# panelDoc.net
KiCad netlist of a schematic drawn in EAGLE
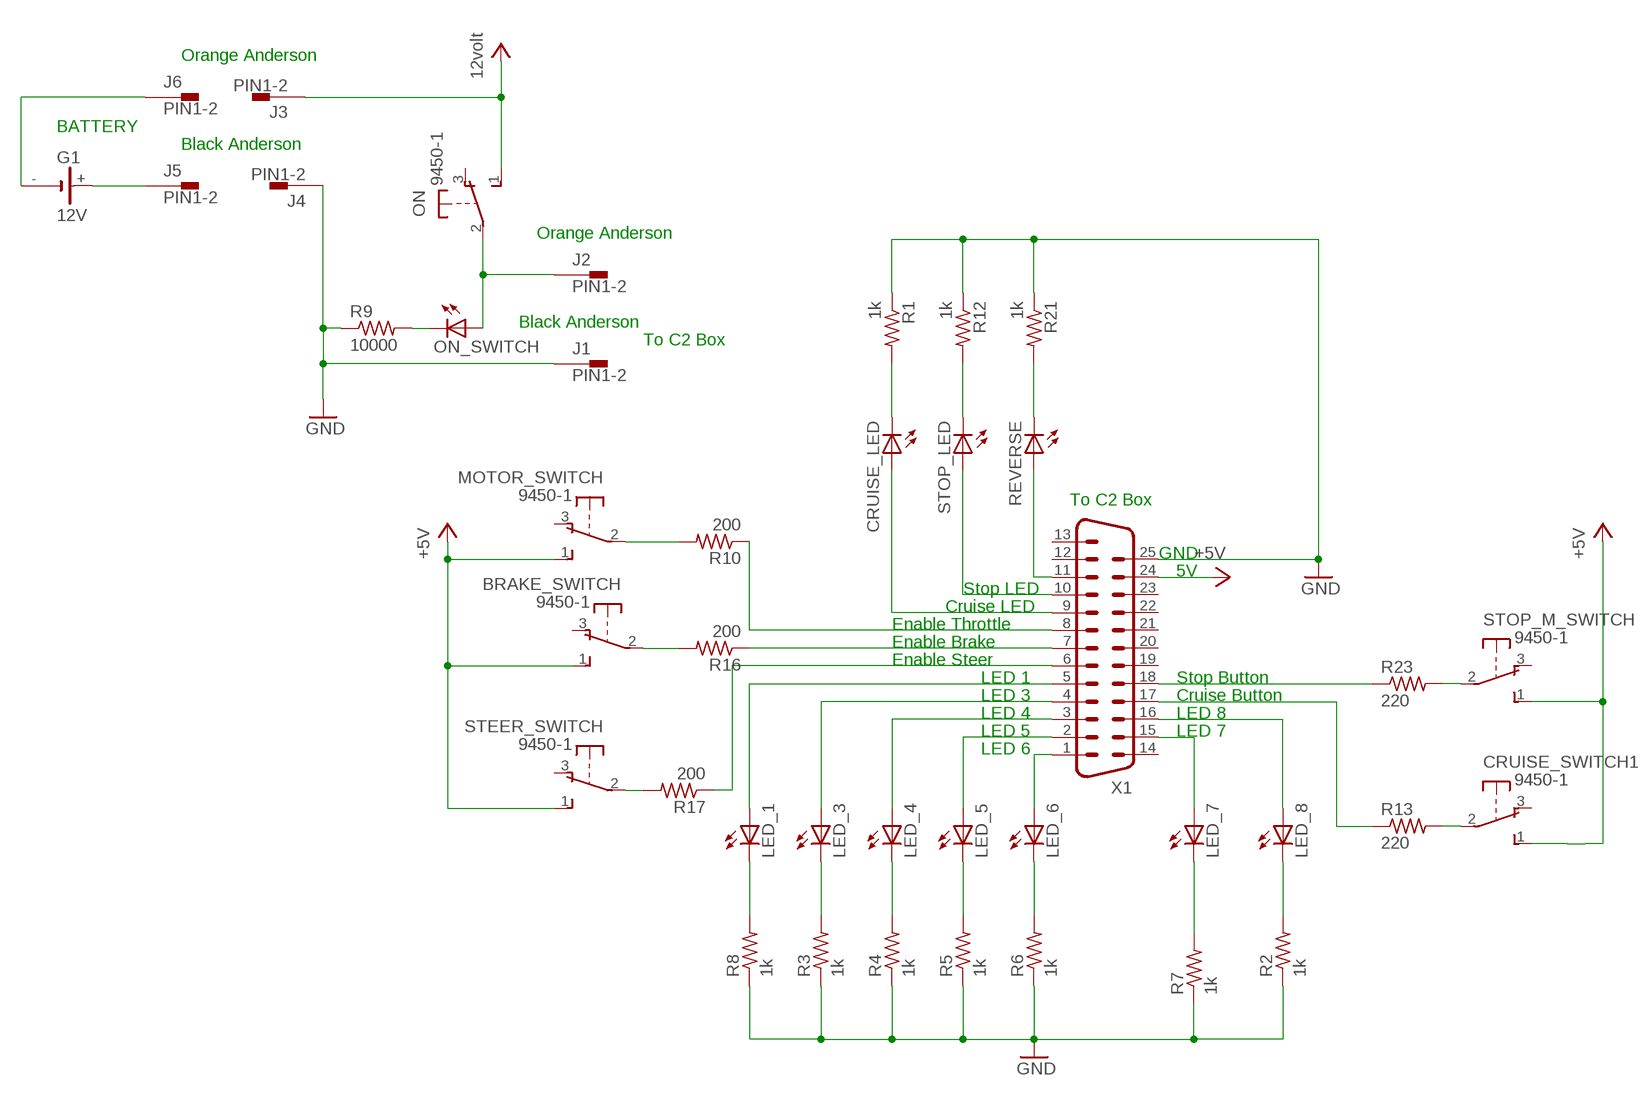
[diagram p0: schematic, sheet 1]

(export (version "E")
  (design (tool "Eeschema 10.0.6"))
  (components
    (comp (ref "BRAKE_SWITCH")
      (value "9450-1")
      (footprint "eagle-import:9450-1")
      (libsource (lib "eagle-import") (part "9450-1"))
    )
    (comp (ref "CRUISE_LED")
      (value "LEDB155")
      (footprint "eagle-import:Q62902-B155")
      (libsource (lib "eagle-import") (part "LEDB155"))
    )
    (comp (ref "CRUISE_SWITCH1")
      (value "9450-1")
      (footprint "eagle-import:9450-1")
      (libsource (lib "eagle-import") (part "9450-1"))
    )
    (comp (ref "G1")
      (value "12V")
      (footprint "eagle-import:SL-150-1_2AA_PT")
      (libsource (lib "eagle-import") (part "SL-150-1/2AA/PT"))
    )
    (comp (ref "J1")
      (value "PIN1-2")
      (footprint "eagle-import:62221")
      (fields (field (name "MF") "TYCO ELECTRONICS") (field (name "MPN") "62221-1"))
      (libsource (lib "eagle-import") (part "PIN1-2"))
    )
    (comp (ref "J2")
      (value "PIN1-2")
      (footprint "eagle-import:62221")
      (fields (field (name "MF") "TYCO ELECTRONICS") (field (name "MPN") "62221-1"))
      (libsource (lib "eagle-import") (part "PIN1-2"))
    )
    (comp (ref "J3")
      (value "PIN1-2")
      (footprint "eagle-import:62221")
      (fields (field (name "MF") "TYCO ELECTRONICS") (field (name "MPN") "62221-1"))
      (libsource (lib "eagle-import") (part "PIN1-2"))
    )
    (comp (ref "J4")
      (value "PIN1-2")
      (footprint "eagle-import:62221")
      (fields (field (name "MF") "TYCO ELECTRONICS") (field (name "MPN") "62221-1"))
      (libsource (lib "eagle-import") (part "PIN1-2"))
    )
    (comp (ref "J5")
      (value "PIN1-2")
      (footprint "eagle-import:62221")
      (fields (field (name "MF") "TYCO ELECTRONICS") (field (name "MPN") "62221-1"))
      (libsource (lib "eagle-import") (part "PIN1-2"))
    )
    (comp (ref "J6")
      (value "PIN1-2")
      (footprint "eagle-import:62221")
      (fields (field (name "MF") "TYCO ELECTRONICS") (field (name "MPN") "62221-1"))
      (libsource (lib "eagle-import") (part "PIN1-2"))
    )
    (comp (ref "LED_1")
      (value "LEDB155")
      (footprint "eagle-import:Q62902-B155")
      (libsource (lib "eagle-import") (part "LEDB155"))
    )
    (comp (ref "LED_3")
      (value "LEDB155")
      (footprint "eagle-import:Q62902-B155")
      (libsource (lib "eagle-import") (part "LEDB155"))
    )
    (comp (ref "LED_4")
      (value "LEDB155")
      (footprint "eagle-import:Q62902-B155")
      (libsource (lib "eagle-import") (part "LEDB155"))
    )
    (comp (ref "LED_5")
      (value "LEDB155")
      (footprint "eagle-import:Q62902-B155")
      (libsource (lib "eagle-import") (part "LEDB155"))
    )
    (comp (ref "LED_6")
      (value "LEDB155")
      (footprint "eagle-import:Q62902-B155")
      (libsource (lib "eagle-import") (part "LEDB155"))
    )
    (comp (ref "LED_7")
      (value "LEDB155")
      (footprint "eagle-import:Q62902-B155")
      (libsource (lib "eagle-import") (part "LEDB155"))
    )
    (comp (ref "LED_8")
      (value "LEDB155")
      (footprint "eagle-import:Q62902-B155")
      (libsource (lib "eagle-import") (part "LEDB155"))
    )
    (comp (ref "MOTOR_SWITCH")
      (value "9450-1")
      (footprint "eagle-import:9450-1")
      (libsource (lib "eagle-import") (part "9450-1"))
    )
    (comp (ref "ON")
      (value "9450-1")
      (footprint "eagle-import:9450-1")
      (libsource (lib "eagle-import") (part "9450-1"))
    )
    (comp (ref "ON_SWITCH")
      (value "LEDB155")
      (footprint "eagle-import:Q62902-B155")
      (libsource (lib "eagle-import") (part "LEDB155"))
    )
    (comp (ref "R1")
      (value "1k")
      (footprint "eagle-import:0617_17")
      (libsource (lib "eagle-import") (part "R-US_0617/17"))
    )
    (comp (ref "R2")
      (value "1k")
      (footprint "eagle-import:0617_17")
      (libsource (lib "eagle-import") (part "R-US_0617/17"))
    )
    (comp (ref "R3")
      (value "1k")
      (footprint "eagle-import:0617_17")
      (libsource (lib "eagle-import") (part "R-US_0617/17"))
    )
    (comp (ref "R4")
      (value "1k")
      (footprint "eagle-import:0617_17")
      (libsource (lib "eagle-import") (part "R-US_0617/17"))
    )
    (comp (ref "R5")
      (value "1k")
      (footprint "eagle-import:0617_17")
      (libsource (lib "eagle-import") (part "R-US_0617/17"))
    )
    (comp (ref "R6")
      (value "1k")
      (footprint "eagle-import:0617_17")
      (libsource (lib "eagle-import") (part "R-US_0617/17"))
    )
    (comp (ref "R7")
      (value "1k")
      (footprint "eagle-import:0617_17")
      (libsource (lib "eagle-import") (part "R-US_0617/17"))
    )
    (comp (ref "R8")
      (value "1k")
      (footprint "eagle-import:0617_17")
      (libsource (lib "eagle-import") (part "R-US_0617/17"))
    )
    (comp (ref "R9")
      (value "10000")
      (footprint "eagle-import:0617_17")
      (libsource (lib "eagle-import") (part "R-US_0617/17"))
    )
    (comp (ref "R10")
      (value "200")
      (footprint "eagle-import:0617_17")
      (libsource (lib "eagle-import") (part "R-US_0617/17"))
    )
    (comp (ref "R12")
      (value "1k")
      (footprint "eagle-import:0617_17")
      (libsource (lib "eagle-import") (part "R-US_0617/17"))
    )
    (comp (ref "R13")
      (value "220")
      (footprint "eagle-import:0617_17")
      (libsource (lib "eagle-import") (part "R-US_0617/17"))
    )
    (comp (ref "R16")
      (value "200")
      (footprint "eagle-import:0617_17")
      (libsource (lib "eagle-import") (part "R-US_0617/17"))
    )
    (comp (ref "R17")
      (value "200")
      (footprint "eagle-import:0617_17")
      (libsource (lib "eagle-import") (part "R-US_0617/17"))
    )
    (comp (ref "R21")
      (value "1k")
      (footprint "eagle-import:0617_17")
      (libsource (lib "eagle-import") (part "R-US_0617/17"))
    )
    (comp (ref "R23")
      (value "220")
      (footprint "eagle-import:0617_17")
      (libsource (lib "eagle-import") (part "R-US_0617/17"))
    )
    (comp (ref "REVERSE")
      (value "LEDB155")
      (footprint "eagle-import:Q62902-B155")
      (libsource (lib "eagle-import") (part "LEDB155"))
    )
    (comp (ref "STEER_SWITCH")
      (value "9450-1")
      (footprint "eagle-import:9450-1")
      (libsource (lib "eagle-import") (part "9450-1"))
    )
    (comp (ref "STOP_LED")
      (value "LEDB155")
      (footprint "eagle-import:Q62902-B155")
      (libsource (lib "eagle-import") (part "LEDB155"))
    )
    (comp (ref "STOP_M_SWITCH")
      (value "9450-1")
      (footprint "eagle-import:9450-1")
      (libsource (lib "eagle-import") (part "9450-1"))
    )
    (comp (ref "X1")
      (value "M25-182")
      (footprint "eagle-import:182-025-MALE")
      (libsource (lib "eagle-import") (part "M25-182"))
    )
  )
  (nets
    (net (code "1") (name "+5V") (class "Default")
      (node (ref "BRAKE_SWITCH") (pin "1") (pinfunction "S_1") (pintype "passive"))
      (node (ref "CRUISE_SWITCH1") (pin "1") (pinfunction "S_1") (pintype "passive"))
      (node (ref "J3") (pin "1") (pinfunction "1_1") (pintype "passive"))
      (node (ref "MOTOR_SWITCH") (pin "1") (pinfunction "S_1") (pintype "passive"))
      (node (ref "ON") (pin "1") (pinfunction "S_1") (pintype "passive"))
      (node (ref "STEER_SWITCH") (pin "1") (pinfunction "S_1") (pintype "passive"))
      (node (ref "STOP_M_SWITCH") (pin "1") (pinfunction "S_1") (pintype "passive"))
      (node (ref "X1") (pin "24") (pinfunction "24_24") (pintype "passive"))
    )
    (net (code "2") (name "GND") (class "Default")
      (node (ref "J1") (pin "1") (pinfunction "1_1") (pintype "passive"))
      (node (ref "J4") (pin "1") (pinfunction "1_1") (pintype "passive"))
      (node (ref "R1") (pin "1") (pinfunction "1_1") (pintype "passive"))
      (node (ref "R12") (pin "1") (pinfunction "1_1") (pintype "passive"))
      (node (ref "R2") (pin "1") (pinfunction "1_1") (pintype "passive"))
      (node (ref "R21") (pin "1") (pinfunction "1_1") (pintype "passive"))
      (node (ref "R3") (pin "1") (pinfunction "1_1") (pintype "passive"))
      (node (ref "R4") (pin "1") (pinfunction "1_1") (pintype "passive"))
      (node (ref "R5") (pin "1") (pinfunction "1_1") (pintype "passive"))
      (node (ref "R6") (pin "1") (pinfunction "1_1") (pintype "passive"))
      (node (ref "R7") (pin "1") (pinfunction "1_1") (pintype "passive"))
      (node (ref "R8") (pin "1") (pinfunction "1_1") (pintype "passive"))
      (node (ref "R9") (pin "1") (pinfunction "1_1") (pintype "passive"))
      (node (ref "X1") (pin "25") (pinfunction "25_25") (pintype "passive"))
    )
    (net (code "3") (name "Net-(BRAKE_SWITCH-P)") (class "Default")
      (node (ref "BRAKE_SWITCH") (pin "2") (pinfunction "P_2") (pintype "passive"))
      (node (ref "R16") (pin "2") (pinfunction "2_2") (pintype "passive"))
    )
    (net (code "4") (name "Net-(CRUISE_LED-C)") (class "Default")
      (node (ref "CRUISE_LED") (pin "K") (pinfunction "C_K") (pintype "passive"))
      (node (ref "R1") (pin "2") (pinfunction "2_2") (pintype "passive"))
    )
    (net (code "5") (name "Net-(CRUISE_LED-PadA)") (class "Default")
      (node (ref "CRUISE_LED") (pin "A") (pinfunction "A_A") (pintype "passive"))
      (node (ref "X1") (pin "9") (pinfunction "9_9") (pintype "passive"))
    )
    (net (code "6") (name "Net-(CRUISE_SWITCH1-P)") (class "Default")
      (node (ref "CRUISE_SWITCH1") (pin "2") (pinfunction "P_2") (pintype "passive"))
      (node (ref "R13") (pin "2") (pinfunction "2_2") (pintype "passive"))
    )
    (net (code "7") (name "Net-(G1-Pad+)") (class "Default")
      (node (ref "G1") (pin "+") (pinfunction "+_+") (pintype "passive"))
      (node (ref "J5") (pin "1") (pinfunction "1_1") (pintype "passive"))
    )
    (net (code "8") (name "Net-(G1-Pad-)") (class "Default")
      (node (ref "G1") (pin "-") (pinfunction "-_-") (pintype "passive"))
      (node (ref "J6") (pin "1") (pinfunction "1_1") (pintype "passive"))
    )
    (net (code "9") (name "Net-(LED_1-C)") (class "Default")
      (node (ref "LED_1") (pin "K") (pinfunction "C_K") (pintype "passive"))
      (node (ref "R8") (pin "2") (pinfunction "2_2") (pintype "passive"))
    )
    (net (code "10") (name "Net-(LED_1-PadA)") (class "Default")
      (node (ref "LED_1") (pin "A") (pinfunction "A_A") (pintype "passive"))
      (node (ref "X1") (pin "5") (pinfunction "5_5") (pintype "passive"))
    )
    (net (code "11") (name "Net-(LED_3-C)") (class "Default")
      (node (ref "LED_3") (pin "K") (pinfunction "C_K") (pintype "passive"))
      (node (ref "R3") (pin "2") (pinfunction "2_2") (pintype "passive"))
    )
    (net (code "12") (name "Net-(LED_3-PadA)") (class "Default")
      (node (ref "LED_3") (pin "A") (pinfunction "A_A") (pintype "passive"))
      (node (ref "X1") (pin "4") (pinfunction "4_4") (pintype "passive"))
    )
    (net (code "13") (name "Net-(LED_4-C)") (class "Default")
      (node (ref "LED_4") (pin "K") (pinfunction "C_K") (pintype "passive"))
      (node (ref "R4") (pin "2") (pinfunction "2_2") (pintype "passive"))
    )
    (net (code "14") (name "Net-(LED_4-PadA)") (class "Default")
      (node (ref "LED_4") (pin "A") (pinfunction "A_A") (pintype "passive"))
      (node (ref "X1") (pin "3") (pinfunction "3_3") (pintype "passive"))
    )
    (net (code "15") (name "Net-(LED_5-C)") (class "Default")
      (node (ref "LED_5") (pin "K") (pinfunction "C_K") (pintype "passive"))
      (node (ref "R5") (pin "2") (pinfunction "2_2") (pintype "passive"))
    )
    (net (code "16") (name "Net-(LED_5-PadA)") (class "Default")
      (node (ref "LED_5") (pin "A") (pinfunction "A_A") (pintype "passive"))
      (node (ref "X1") (pin "2") (pinfunction "2_2") (pintype "passive"))
    )
    (net (code "17") (name "Net-(LED_6-C)") (class "Default")
      (node (ref "LED_6") (pin "K") (pinfunction "C_K") (pintype "passive"))
      (node (ref "R6") (pin "2") (pinfunction "2_2") (pintype "passive"))
    )
    (net (code "18") (name "Net-(LED_6-PadA)") (class "Default")
      (node (ref "LED_6") (pin "A") (pinfunction "A_A") (pintype "passive"))
      (node (ref "X1") (pin "1") (pinfunction "1_1") (pintype "passive"))
    )
    (net (code "19") (name "Net-(LED_7-C)") (class "Default")
      (node (ref "LED_7") (pin "K") (pinfunction "C_K") (pintype "passive"))
      (node (ref "R7") (pin "2") (pinfunction "2_2") (pintype "passive"))
    )
    (net (code "20") (name "Net-(LED_7-PadA)") (class "Default")
      (node (ref "LED_7") (pin "A") (pinfunction "A_A") (pintype "passive"))
      (node (ref "X1") (pin "15") (pinfunction "15_15") (pintype "passive"))
    )
    (net (code "21") (name "Net-(LED_8-C)") (class "Default")
      (node (ref "LED_8") (pin "K") (pinfunction "C_K") (pintype "passive"))
      (node (ref "R2") (pin "2") (pinfunction "2_2") (pintype "passive"))
    )
    (net (code "22") (name "Net-(LED_8-PadA)") (class "Default")
      (node (ref "LED_8") (pin "A") (pinfunction "A_A") (pintype "passive"))
      (node (ref "X1") (pin "16") (pinfunction "16_16") (pintype "passive"))
    )
    (net (code "23") (name "Net-(MOTOR_SWITCH-P)") (class "Default")
      (node (ref "MOTOR_SWITCH") (pin "2") (pinfunction "P_2") (pintype "passive"))
      (node (ref "R10") (pin "2") (pinfunction "2_2") (pintype "passive"))
    )
    (net (code "24") (name "Net-(ON-P)") (class "Default")
      (node (ref "J2") (pin "1") (pinfunction "1_1") (pintype "passive"))
      (node (ref "ON") (pin "2") (pinfunction "P_2") (pintype "passive"))
      (node (ref "ON_SWITCH") (pin "A") (pinfunction "A_A") (pintype "passive"))
    )
    (net (code "25") (name "Net-(ON_SWITCH-C)") (class "Default")
      (node (ref "ON_SWITCH") (pin "K") (pinfunction "C_K") (pintype "passive"))
      (node (ref "R9") (pin "2") (pinfunction "2_2") (pintype "passive"))
    )
    (net (code "26") (name "Net-(R10-Pad1)") (class "Default")
      (node (ref "R10") (pin "1") (pinfunction "1_1") (pintype "passive"))
      (node (ref "X1") (pin "8") (pinfunction "8_8") (pintype "passive"))
    )
    (net (code "27") (name "Net-(R13-Pad1)") (class "Default")
      (node (ref "R13") (pin "1") (pinfunction "1_1") (pintype "passive"))
      (node (ref "X1") (pin "17") (pinfunction "17_17") (pintype "passive"))
    )
    (net (code "28") (name "Net-(R16-Pad1)") (class "Default")
      (node (ref "R16") (pin "1") (pinfunction "1_1") (pintype "passive"))
      (node (ref "X1") (pin "7") (pinfunction "7_7") (pintype "passive"))
    )
    (net (code "29") (name "Net-(R17-Pad1)") (class "Default")
      (node (ref "R17") (pin "1") (pinfunction "1_1") (pintype "passive"))
      (node (ref "X1") (pin "6") (pinfunction "6_6") (pintype "passive"))
    )
    (net (code "30") (name "Net-(R23-Pad1)") (class "Default")
      (node (ref "R23") (pin "1") (pinfunction "1_1") (pintype "passive"))
      (node (ref "X1") (pin "18") (pinfunction "18_18") (pintype "passive"))
    )
    (net (code "31") (name "Net-(REVERSE-C)") (class "Default")
      (node (ref "R21") (pin "2") (pinfunction "2_2") (pintype "passive"))
      (node (ref "REVERSE") (pin "K") (pinfunction "C_K") (pintype "passive"))
    )
    (net (code "32") (name "Net-(REVERSE-PadA)") (class "Default")
      (node (ref "REVERSE") (pin "A") (pinfunction "A_A") (pintype "passive"))
      (node (ref "X1") (pin "11") (pinfunction "11_11") (pintype "passive"))
    )
    (net (code "33") (name "Net-(STEER_SWITCH-P)") (class "Default")
      (node (ref "R17") (pin "2") (pinfunction "2_2") (pintype "passive"))
      (node (ref "STEER_SWITCH") (pin "2") (pinfunction "P_2") (pintype "passive"))
    )
    (net (code "34") (name "Net-(STOP_LED-C)") (class "Default")
      (node (ref "R12") (pin "2") (pinfunction "2_2") (pintype "passive"))
      (node (ref "STOP_LED") (pin "K") (pinfunction "C_K") (pintype "passive"))
    )
    (net (code "35") (name "Net-(STOP_LED-PadA)") (class "Default")
      (node (ref "STOP_LED") (pin "A") (pinfunction "A_A") (pintype "passive"))
      (node (ref "X1") (pin "10") (pinfunction "10_10") (pintype "passive"))
    )
    (net (code "36") (name "Net-(STOP_M_SWITCH-P)") (class "Default")
      (node (ref "R23") (pin "2") (pinfunction "2_2") (pintype "passive"))
      (node (ref "STOP_M_SWITCH") (pin "2") (pinfunction "P_2") (pintype "passive"))
    )
    (net (code "37") (name "unconnected-(BRAKE_SWITCH-O-Pad3)") (class "Default")
      (node (ref "BRAKE_SWITCH") (pin "3") (pinfunction "O_3") (pintype "passive"))
    )
    (net (code "38") (name "unconnected-(CRUISE_SWITCH1-O-Pad3)") (class "Default")
      (node (ref "CRUISE_SWITCH1") (pin "3") (pinfunction "O_3") (pintype "passive"))
    )
    (net (code "39") (name "unconnected-(G1---Pad-@1)") (class "Default")
      (node (ref "G1") (pin "-@1") (pinfunction "-_-@1") (pintype "passive"))
    )
    (net (code "40") (name "unconnected-(MOTOR_SWITCH-O-Pad3)") (class "Default")
      (node (ref "MOTOR_SWITCH") (pin "3") (pinfunction "O_3") (pintype "passive"))
    )
    (net (code "41") (name "unconnected-(ON-O-Pad3)") (class "Default")
      (node (ref "ON") (pin "3") (pinfunction "O_3") (pintype "passive"))
    )
    (net (code "42") (name "unconnected-(STEER_SWITCH-O-Pad3)") (class "Default")
      (node (ref "STEER_SWITCH") (pin "3") (pinfunction "O_3") (pintype "passive"))
    )
    (net (code "43") (name "unconnected-(STOP_M_SWITCH-O-Pad3)") (class "Default")
      (node (ref "STOP_M_SWITCH") (pin "3") (pinfunction "O_3") (pintype "passive"))
    )
    (net (code "44") (name "unconnected-(X1-Pad12)") (class "Default")
      (node (ref "X1") (pin "12") (pinfunction "12_12") (pintype "passive"))
    )
    (net (code "45") (name "unconnected-(X1-Pad13)") (class "Default")
      (node (ref "X1") (pin "13") (pinfunction "13_13") (pintype "passive"))
    )
    (net (code "46") (name "unconnected-(X1-Pad14)") (class "Default")
      (node (ref "X1") (pin "14") (pinfunction "14_14") (pintype "passive"))
    )
    (net (code "47") (name "unconnected-(X1-Pad19)") (class "Default")
      (node (ref "X1") (pin "19") (pinfunction "19_19") (pintype "passive"))
    )
    (net (code "48") (name "unconnected-(X1-Pad20)") (class "Default")
      (node (ref "X1") (pin "20") (pinfunction "20_20") (pintype "passive"))
    )
    (net (code "49") (name "unconnected-(X1-Pad21)") (class "Default")
      (node (ref "X1") (pin "21") (pinfunction "21_21") (pintype "passive"))
    )
    (net (code "50") (name "unconnected-(X1-Pad22)") (class "Default")
      (node (ref "X1") (pin "22") (pinfunction "22_22") (pintype "passive"))
    )
    (net (code "51") (name "unconnected-(X1-Pad23)") (class "Default")
      (node (ref "X1") (pin "23") (pinfunction "23_23") (pintype "passive"))
    )
  )
)
